# DualEncoderBoard-revc.net
KiCad netlist of a schematic drawn in EAGLE
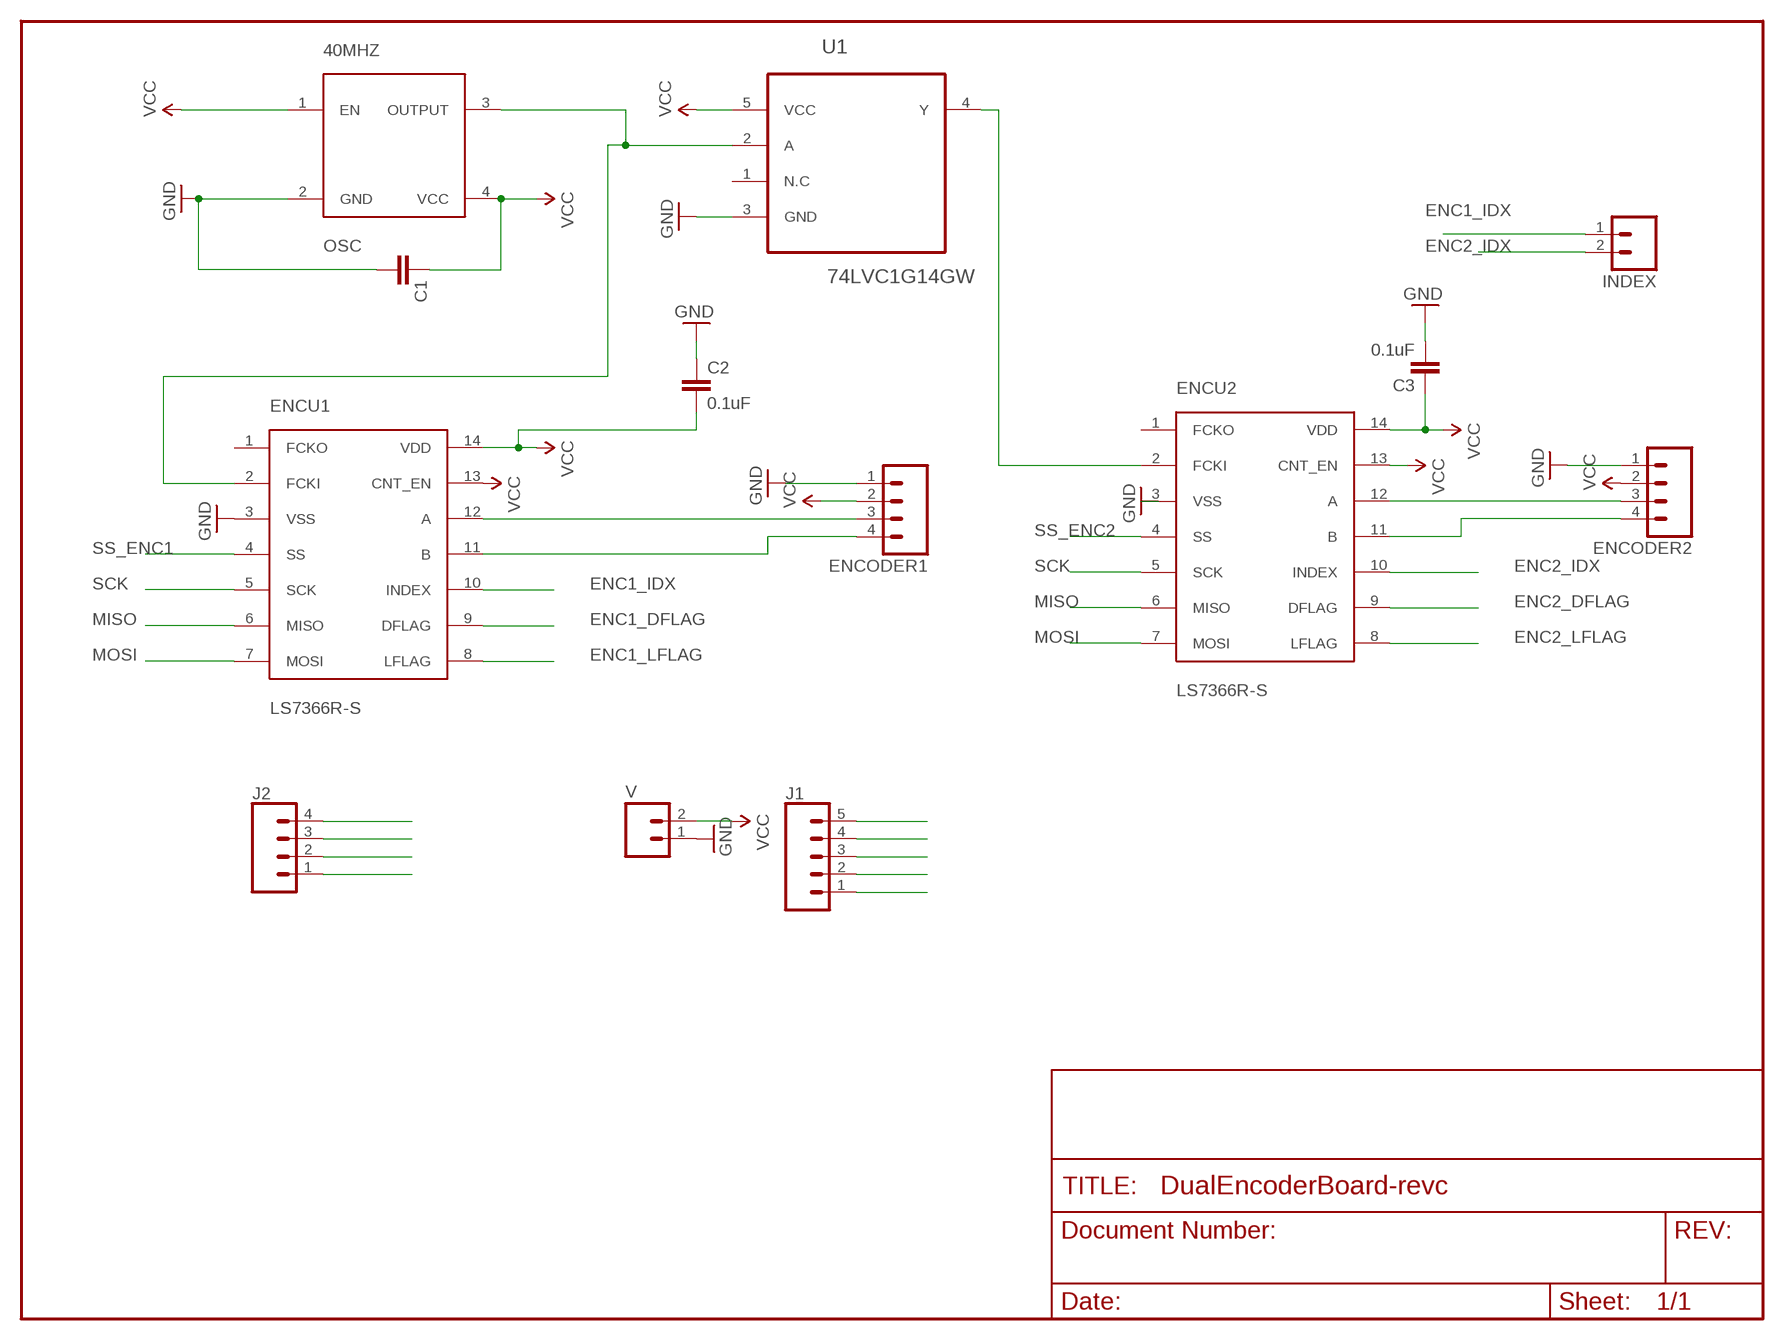
[diagram p0: schematic, sheet 1]

(export (version "E")
  (design (tool "Eeschema 10.0.6"))
  (components
    (comp (ref "40MHZ")
      (value "OSC")
      (footprint "eagle-import:CB3OSCILLATOR")
      (libsource (lib "eagle-import") (part "OSC"))
    )
    (comp (ref "C1")
      (value "CAPKIT")
      (footprint "eagle-import:CAP-PTH-SMALL-KIT")
      (libsource (lib "eagle-import") (part "CAPKIT"))
    )
    (comp (ref "C2")
      (value "0.1uF")
      (footprint "eagle-import:0603")
      (libsource (lib "eagle-import") (part "0.1UF-0603-25V-5%"))
    )
    (comp (ref "C3")
      (value "0.1uF")
      (footprint "eagle-import:0603")
      (libsource (lib "eagle-import") (part "0.1UF-0603-25V-5%"))
    )
    (comp (ref "ENCODER1")
      (value "M04POLAR")
      (footprint "eagle-import:MOLEX-1X4")
      (libsource (lib "eagle-import") (part "M04POLAR"))
    )
    (comp (ref "ENCODER2")
      (value "M04POLAR")
      (footprint "eagle-import:MOLEX-1X4")
      (libsource (lib "eagle-import") (part "M04POLAR"))
    )
    (comp (ref "ENCU1")
      (value "LS7366R-S")
      (footprint "eagle-import:SO14")
      (libsource (lib "eagle-import") (part "LS7366R-S"))
    )
    (comp (ref "ENCU2")
      (value "LS7366R-S")
      (footprint "eagle-import:SO14")
      (libsource (lib "eagle-import") (part "LS7366R-S"))
    )
    (comp (ref "INDEX")
      (value "M02PTH")
      (footprint "eagle-import:1X02")
      (libsource (lib "eagle-import") (part "M02PTH"))
    )
    (comp (ref "J1")
      (value "CONN_05")
      (footprint "eagle-import:1X05")
      (libsource (lib "eagle-import") (part "CONN_05"))
    )
    (comp (ref "J2")
      (value "CONN_04")
      (footprint "eagle-import:1X04")
      (libsource (lib "eagle-import") (part "CONN_04"))
    )
    (comp (ref "U1")
      (value "74LVC1G14GW")
      (footprint "eagle-import:SOT65P210X110-5N")
      (fields (field (name "MF") "NXP Semiconductors"))
      (libsource (lib "eagle-import") (part "74LVC1G14GW"))
    )
    (comp (ref "V")
      (value "M02-JST-2MM-SMT")
      (footprint "eagle-import:JST-2-SMD")
      (libsource (lib "eagle-import") (part "M02-JST-2MM-SMT"))
    )
  )
  (nets
    (net (code "1") (name "/ENC1_DFLAG") (class "Default")
      (node (ref "ENCU1") (pin "9") (pinfunction "DFLAG_9") (pintype "output"))
      (node (ref "J2") (pin "4") (pinfunction "4_4") (pintype "passive"))
    )
    (net (code "2") (name "/ENC1_IDX") (class "Default")
      (node (ref "ENCU1") (pin "10") (pinfunction "INDEX_10") (pintype "input"))
      (node (ref "INDEX") (pin "1") (pinfunction "1_1") (pintype "passive"))
    )
    (net (code "3") (name "/ENC1_LFLAG") (class "Default")
      (node (ref "ENCU1") (pin "8") (pinfunction "LFLAG_8") (pintype "output"))
      (node (ref "J2") (pin "3") (pinfunction "3_3") (pintype "passive"))
    )
    (net (code "4") (name "/ENC2_DFLAG") (class "Default")
      (node (ref "ENCU2") (pin "9") (pinfunction "DFLAG_9") (pintype "output"))
      (node (ref "J2") (pin "2") (pinfunction "2_2") (pintype "passive"))
    )
    (net (code "5") (name "/ENC2_IDX") (class "Default")
      (node (ref "ENCU2") (pin "10") (pinfunction "INDEX_10") (pintype "input"))
      (node (ref "INDEX") (pin "2") (pinfunction "2_2") (pintype "passive"))
    )
    (net (code "6") (name "/ENC2_LFLAG") (class "Default")
      (node (ref "ENCU2") (pin "8") (pinfunction "LFLAG_8") (pintype "output"))
      (node (ref "J2") (pin "1") (pinfunction "1_1") (pintype "passive"))
    )
    (net (code "7") (name "/MISO") (class "Default")
      (node (ref "ENCU1") (pin "6") (pinfunction "MISO_6") (pintype "output"))
      (node (ref "ENCU2") (pin "6") (pinfunction "MISO_6") (pintype "output"))
      (node (ref "J1") (pin "2") (pinfunction "2_2") (pintype "passive"))
    )
    (net (code "8") (name "/MOSI") (class "Default")
      (node (ref "ENCU1") (pin "7") (pinfunction "MOSI_7") (pintype "input"))
      (node (ref "ENCU2") (pin "7") (pinfunction "MOSI_7") (pintype "input"))
      (node (ref "J1") (pin "1") (pinfunction "1_1") (pintype "passive"))
    )
    (net (code "9") (name "/SCK") (class "Default")
      (node (ref "ENCU1") (pin "5") (pinfunction "SCK_5") (pintype "input"))
      (node (ref "ENCU2") (pin "5") (pinfunction "SCK_5") (pintype "input"))
      (node (ref "J1") (pin "3") (pinfunction "3_3") (pintype "passive"))
    )
    (net (code "10") (name "/SS_ENC1") (class "Default")
      (node (ref "ENCU1") (pin "4") (pinfunction "SS_4") (pintype "input"))
      (node (ref "J1") (pin "5") (pinfunction "5_5") (pintype "passive"))
    )
    (net (code "11") (name "/SS_ENC2") (class "Default")
      (node (ref "ENCU2") (pin "4") (pinfunction "SS_4") (pintype "input"))
      (node (ref "J1") (pin "4") (pinfunction "4_4") (pintype "passive"))
    )
    (net (code "12") (name "GND") (class "Default")
      (node (ref "40MHZ") (pin "2") (pinfunction "GND_2") (pintype "input"))
      (node (ref "C1") (pin "2") (pinfunction "2_2") (pintype "passive"))
      (node (ref "C2") (pin "1") (pinfunction "1_1") (pintype "passive"))
      (node (ref "C3") (pin "2") (pinfunction "2_2") (pintype "passive"))
      (node (ref "ENCODER1") (pin "1") (pinfunction "1_1") (pintype "passive"))
      (node (ref "ENCODER2") (pin "1") (pinfunction "1_1") (pintype "passive"))
      (node (ref "ENCU1") (pin "3") (pinfunction "VSS_3") (pintype "power_in"))
      (node (ref "ENCU2") (pin "3") (pinfunction "VSS_3") (pintype "power_in"))
      (node (ref "U1") (pin "3") (pinfunction "GND_3") (pintype "passive"))
      (node (ref "V") (pin "1") (pinfunction "1_1") (pintype "passive"))
    )
    (net (code "13") (name "Net-(40MHZ-OUTPUT)") (class "Default")
      (node (ref "40MHZ") (pin "3") (pinfunction "OUTPUT_3") (pintype "output"))
      (node (ref "ENCU1") (pin "2") (pinfunction "FCKI_2") (pintype "input"))
      (node (ref "U1") (pin "2") (pinfunction "A_2") (pintype "input"))
    )
    (net (code "14") (name "Net-(ENCU1-A)") (class "Default")
      (node (ref "ENCODER1") (pin "3") (pinfunction "3_3") (pintype "passive"))
      (node (ref "ENCU1") (pin "12") (pinfunction "A_12") (pintype "input"))
    )
    (net (code "15") (name "Net-(ENCU1-B)") (class "Default")
      (node (ref "ENCODER1") (pin "4") (pinfunction "4_4") (pintype "passive"))
      (node (ref "ENCU1") (pin "11") (pinfunction "B_11") (pintype "input"))
    )
    (net (code "16") (name "Net-(ENCU2-A)") (class "Default")
      (node (ref "ENCODER2") (pin "3") (pinfunction "3_3") (pintype "passive"))
      (node (ref "ENCU2") (pin "12") (pinfunction "A_12") (pintype "input"))
    )
    (net (code "17") (name "Net-(ENCU2-B)") (class "Default")
      (node (ref "ENCODER2") (pin "4") (pinfunction "4_4") (pintype "passive"))
      (node (ref "ENCU2") (pin "11") (pinfunction "B_11") (pintype "input"))
    )
    (net (code "18") (name "Net-(ENCU2-FCKI)") (class "Default")
      (node (ref "ENCU2") (pin "2") (pinfunction "FCKI_2") (pintype "input"))
      (node (ref "U1") (pin "4") (pinfunction "Y_4") (pintype "output"))
    )
    (net (code "19") (name "VCC") (class "Default")
      (node (ref "40MHZ") (pin "1") (pinfunction "EN_1") (pintype "input"))
      (node (ref "40MHZ") (pin "4") (pinfunction "VCC_4") (pintype "input"))
      (node (ref "C1") (pin "1") (pinfunction "1_1") (pintype "passive"))
      (node (ref "C2") (pin "2") (pinfunction "2_2") (pintype "passive"))
      (node (ref "C3") (pin "1") (pinfunction "1_1") (pintype "passive"))
      (node (ref "ENCODER1") (pin "2") (pinfunction "2_2") (pintype "passive"))
      (node (ref "ENCODER2") (pin "2") (pinfunction "2_2") (pintype "passive"))
      (node (ref "ENCU1") (pin "13") (pinfunction "CNT_EN_13") (pintype "input"))
      (node (ref "ENCU1") (pin "14") (pinfunction "VDD_14") (pintype "power_in"))
      (node (ref "ENCU2") (pin "13") (pinfunction "CNT_EN_13") (pintype "input"))
      (node (ref "ENCU2") (pin "14") (pinfunction "VDD_14") (pintype "power_in"))
      (node (ref "U1") (pin "5") (pinfunction "VCC_5") (pintype "power_in"))
      (node (ref "V") (pin "2") (pinfunction "2_2") (pintype "passive"))
    )
    (net (code "20") (name "unconnected-(ENCU1-FCKO-Pad1)") (class "Default")
      (node (ref "ENCU1") (pin "1") (pinfunction "FCKO_1") (pintype "output"))
    )
    (net (code "21") (name "unconnected-(ENCU2-FCKO-Pad1)") (class "Default")
      (node (ref "ENCU2") (pin "1") (pinfunction "FCKO_1") (pintype "output"))
    )
    (net (code "22") (name "unconnected-(U1-N.C-Pad1)") (class "Default")
      (node (ref "U1") (pin "1") (pinfunction "N.C_1") (pintype "no_connect"))
    )
  )
)
